# Sheet2.net
KiCad netlist of a schematic drawn in Altium Designer
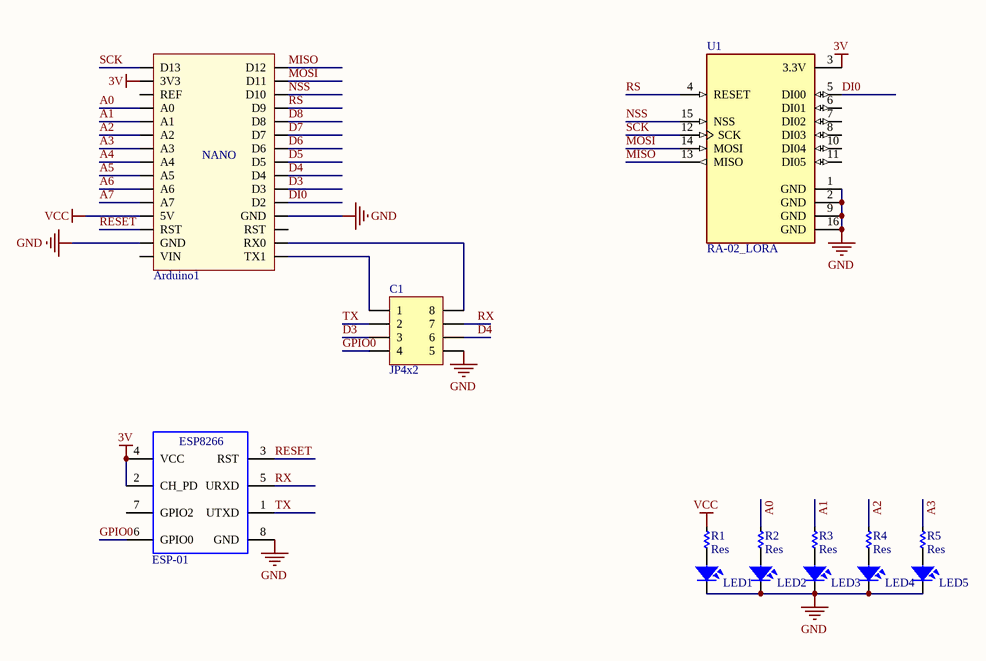
[diagram p0: Sheet2.SchDoc]

(export (version "E")
  (design (tool "Eeschema 10.0.6"))
  (components
    (comp (ref "Arduino1")
      (value "Arduino Nano")
      (footprint "Arduino Nano")
      (description "Arduino NANO")
      (libsource (lib "LIBRARY") (part "Arduino Nano"))
    )
    (comp (ref "C1")
      (value "JP4x2")
      (footprint "JP4-D2T")
      (description "WR-PHD 2.54 mm Dual Socket Header")
      (fields
        (field (name "MANUFACTURER") "Würth Elektronik eiSos GmbH")
        (field (name "PARTNO") "61300821821")
        (field (name "CREATED BY") "Karrer Zheng")
      )
      (libsource (lib "LIBRARY") (part "JP4x2"))
    )
    (comp (ref "LED1")
      (value "LED")
      (footprint "LED-5-Yellow")
      (description "LED Single colour Green and Red")
      (libsource (lib "LIBRARY") (part "LED"))
    )
    (comp (ref "LED2")
      (value "LED")
      (footprint "LED-5-Yellow")
      (description "LED Single colour Green and Red")
      (libsource (lib "LIBRARY") (part "LED"))
    )
    (comp (ref "LED3")
      (value "LED")
      (footprint "LED-5-Yellow")
      (description "LED Single colour Green and Red")
      (libsource (lib "LIBRARY") (part "LED"))
    )
    (comp (ref "LED4")
      (value "LED")
      (footprint "LED-5-Yellow")
      (description "LED Single colour Green and Red")
      (libsource (lib "LIBRARY") (part "LED"))
    )
    (comp (ref "LED5")
      (value "LED")
      (footprint "LED-5-Yellow")
      (description "LED Single colour Green and Red")
      (libsource (lib "LIBRARY") (part "LED"))
    )
    (comp (ref "R1")
      (value "Res")
      (footprint "RES-1/4WD")
      (fields
        (field (name "MANUFACTURER") "Generic Components")
        (field (name "PUBLISHER") "Altium Hobart Technology Centre")
      )
      (libsource (lib "LIBRARY") (part "Res"))
    )
    (comp (ref "R2")
      (value "Res")
      (footprint "RES-1/4WD")
      (fields
        (field (name "MANUFACTURER") "Generic Components")
        (field (name "PUBLISHER") "Altium Hobart Technology Centre")
      )
      (libsource (lib "LIBRARY") (part "Res"))
    )
    (comp (ref "R3")
      (value "Res")
      (footprint "RES-1/4WD")
      (fields
        (field (name "MANUFACTURER") "Generic Components")
        (field (name "PUBLISHER") "Altium Hobart Technology Centre")
      )
      (libsource (lib "LIBRARY") (part "Res"))
    )
    (comp (ref "R4")
      (value "Res")
      (footprint "RES-1/4WD")
      (fields
        (field (name "MANUFACTURER") "Generic Components")
        (field (name "PUBLISHER") "Altium Hobart Technology Centre")
      )
      (libsource (lib "LIBRARY") (part "Res"))
    )
    (comp (ref "R5")
      (value "Res")
      (footprint "RES-1/4WD")
      (fields
        (field (name "MANUFACTURER") "Generic Components")
        (field (name "PUBLISHER") "Altium Hobart Technology Centre")
      )
      (libsource (lib "LIBRARY") (part "Res"))
    )
    (comp (ref "U1")
      (value "RA-02_LORA")
      (footprint "MODULE_RA-02_LORA")
      (description "Ra-02 LoRa RF M5Stack Platform Evaluation Expansion Board")
      (fields (field (name "MP") "Ra-02 LoRa") (field (name "MF") "AI-Thinker"))
      (libsource (lib "RA-02_LORA") (part "RA-02_LORA"))
    )
    (comp (ref "U2")
      (value "ESP-01")
      (footprint "ESP8266")
      (description "ESP-12 Wi-Fi Module")
      (libsource (lib "LIBRARY") (part "ESP8266-01"))
    )
  )
  (nets
    (net (code "1") (name "/A0") (class "Default")
      (node (ref "Arduino1") (pin "A0") (pinfunction "A0_A0") (pintype "passive"))
      (node (ref "R2") (pin "1") (pinfunction "1_1") (pintype "passive"))
    )
    (net (code "2") (name "/A1") (class "Default")
      (node (ref "Arduino1") (pin "A1") (pinfunction "A1_A1") (pintype "passive"))
      (node (ref "R3") (pin "1") (pinfunction "1_1") (pintype "passive"))
    )
    (net (code "3") (name "/A2") (class "Default")
      (node (ref "Arduino1") (pin "A2") (pinfunction "A2_A2") (pintype "passive"))
      (node (ref "R4") (pin "1") (pinfunction "1_1") (pintype "passive"))
    )
    (net (code "4") (name "/A3") (class "Default")
      (node (ref "Arduino1") (pin "A3") (pinfunction "A3_A3") (pintype "passive"))
      (node (ref "R5") (pin "1") (pinfunction "1_1") (pintype "passive"))
    )
    (net (code "5") (name "/A4") (class "Default")
      (node (ref "Arduino1") (pin "A4") (pinfunction "A4_A4") (pintype "passive"))
    )
    (net (code "6") (name "/A5") (class "Default")
      (node (ref "Arduino1") (pin "A5") (pinfunction "A5_A5") (pintype "passive"))
    )
    (net (code "7") (name "/A6") (class "Default")
      (node (ref "Arduino1") (pin "A6") (pinfunction "A6_A6") (pintype "passive"))
    )
    (net (code "8") (name "/A7") (class "Default")
      (node (ref "Arduino1") (pin "A7") (pinfunction "A7_A7") (pintype "passive"))
    )
    (net (code "9") (name "/D3") (class "Default")
      (node (ref "Arduino1") (pin "D3") (pinfunction "D3_D3") (pintype "passive"))
      (node (ref "C1") (pin "3") (pinfunction "3_3") (pintype "passive"))
    )
    (net (code "10") (name "/D4") (class "Default")
      (node (ref "Arduino1") (pin "D4") (pinfunction "D4_D4") (pintype "passive"))
      (node (ref "C1") (pin "6") (pinfunction "6_6") (pintype "passive"))
    )
    (net (code "11") (name "/D5") (class "Default")
      (node (ref "Arduino1") (pin "D5") (pinfunction "D5_D5") (pintype "passive"))
    )
    (net (code "12") (name "/D6") (class "Default")
      (node (ref "Arduino1") (pin "D6") (pinfunction "D6_D6") (pintype "passive"))
    )
    (net (code "13") (name "/D7") (class "Default")
      (node (ref "Arduino1") (pin "D7") (pinfunction "D7_D7") (pintype "passive"))
    )
    (net (code "14") (name "/D8") (class "Default")
      (node (ref "Arduino1") (pin "D8") (pinfunction "D8_D8") (pintype "passive"))
    )
    (net (code "15") (name "/DI0") (class "Default")
      (node (ref "Arduino1") (pin "D2") (pinfunction "D2_D2") (pintype "passive"))
      (node (ref "U1") (pin "5") (pinfunction "DI00_5") (pintype "bidirectional"))
    )
    (net (code "16") (name "/GPIO0") (class "Default")
      (node (ref "C1") (pin "4") (pinfunction "4_4") (pintype "passive"))
      (node (ref "U2") (pin "6") (pinfunction "GPIO0_6") (pintype "passive"))
    )
    (net (code "17") (name "/MISO") (class "Default")
      (node (ref "Arduino1") (pin "D12") (pinfunction "D12_D12") (pintype "passive"))
      (node (ref "U1") (pin "13") (pinfunction "MISO_13") (pintype "output"))
    )
    (net (code "18") (name "/MOSI") (class "Default")
      (node (ref "Arduino1") (pin "D11") (pinfunction "D11_D11") (pintype "passive"))
      (node (ref "U1") (pin "14") (pinfunction "MOSI_14") (pintype "input"))
    )
    (net (code "19") (name "/NSS") (class "Default")
      (node (ref "Arduino1") (pin "D10") (pinfunction "D10_D10") (pintype "passive"))
      (node (ref "U1") (pin "15") (pinfunction "NSS_15") (pintype "input"))
    )
    (net (code "20") (name "/RESET") (class "Default")
      (node (ref "Arduino1") (pin "RST") (pinfunction "RST_RST") (pintype "passive"))
      (node (ref "U2") (pin "3") (pinfunction "RST_3") (pintype "passive"))
    )
    (net (code "21") (name "/RS") (class "Default")
      (node (ref "Arduino1") (pin "D9") (pinfunction "D9_D9") (pintype "passive"))
      (node (ref "U1") (pin "4") (pinfunction "RESET_4") (pintype "input"))
    )
    (net (code "22") (name "/RX") (class "Default")
      (node (ref "C1") (pin "7") (pinfunction "7_7") (pintype "passive"))
      (node (ref "U2") (pin "5") (pinfunction "URXD_5") (pintype "passive"))
    )
    (net (code "23") (name "/SCK") (class "Default")
      (node (ref "Arduino1") (pin "D13") (pinfunction "D13_D13") (pintype "passive"))
      (node (ref "U1") (pin "12") (pinfunction "SCK_12") (pintype "input"))
    )
    (net (code "24") (name "/TX") (class "Default")
      (node (ref "C1") (pin "2") (pinfunction "2_2") (pintype "passive"))
      (node (ref "U2") (pin "1") (pinfunction "UTXD_1") (pintype "passive"))
    )
    (net (code "25") (name "3V") (class "Default")
      (node (ref "Arduino1") (pin "3V3") (pinfunction "3V3_3V3") (pintype "passive"))
      (node (ref "U1") (pin "3") (pinfunction "3.3V_3") (pintype "power_in"))
      (node (ref "U2") (pin "2") (pinfunction "CH_PD_2") (pintype "passive"))
      (node (ref "U2") (pin "4") (pinfunction "VCC_4") (pintype "passive"))
    )
    (net (code "26") (name "GND") (class "Default")
      (node (ref "Arduino1") (pin "GND") (pinfunction "GND_GND") (pintype "passive"))
      (node (ref "C1") (pin "5") (pinfunction "5_5") (pintype "passive"))
      (node (ref "LED1") (pin "2") (pinfunction "2_2") (pintype "passive"))
      (node (ref "LED2") (pin "2") (pinfunction "2_2") (pintype "passive"))
      (node (ref "LED3") (pin "2") (pinfunction "2_2") (pintype "passive"))
      (node (ref "LED4") (pin "2") (pinfunction "2_2") (pintype "passive"))
      (node (ref "LED5") (pin "2") (pinfunction "2_2") (pintype "passive"))
      (node (ref "U1") (pin "1") (pinfunction "GND_1") (pintype "power_in"))
      (node (ref "U1") (pin "16") (pinfunction "GND_16") (pintype "power_in"))
      (node (ref "U1") (pin "2") (pinfunction "GND_2") (pintype "power_in"))
      (node (ref "U1") (pin "9") (pinfunction "GND_9") (pintype "power_in"))
      (node (ref "U2") (pin "8") (pinfunction "GND_8") (pintype "passive"))
    )
    (net (code "27") (name "Net-(Arduino1-PadRX0)") (class "Default")
      (node (ref "Arduino1") (pin "RX0") (pinfunction "RX0_RX0") (pintype "passive"))
      (node (ref "C1") (pin "8") (pinfunction "8_8") (pintype "passive"))
    )
    (net (code "28") (name "Net-(Arduino1-PadTX1)") (class "Default")
      (node (ref "Arduino1") (pin "TX1") (pinfunction "TX1_TX1") (pintype "passive"))
      (node (ref "C1") (pin "1") (pinfunction "1_1") (pintype "passive"))
    )
    (net (code "29") (name "Net-(LED1-Pad1)") (class "Default")
      (node (ref "LED1") (pin "1") (pinfunction "1_1") (pintype "passive"))
      (node (ref "R1") (pin "2") (pinfunction "2_2") (pintype "passive"))
    )
    (net (code "30") (name "Net-(LED2-Pad1)") (class "Default")
      (node (ref "LED2") (pin "1") (pinfunction "1_1") (pintype "passive"))
      (node (ref "R2") (pin "2") (pinfunction "2_2") (pintype "passive"))
    )
    (net (code "31") (name "Net-(LED3-Pad1)") (class "Default")
      (node (ref "LED3") (pin "1") (pinfunction "1_1") (pintype "passive"))
      (node (ref "R3") (pin "2") (pinfunction "2_2") (pintype "passive"))
    )
    (net (code "32") (name "Net-(LED4-Pad1)") (class "Default")
      (node (ref "LED4") (pin "1") (pinfunction "1_1") (pintype "passive"))
      (node (ref "R4") (pin "2") (pinfunction "2_2") (pintype "passive"))
    )
    (net (code "33") (name "Net-(LED5-Pad1)") (class "Default")
      (node (ref "LED5") (pin "1") (pinfunction "1_1") (pintype "passive"))
      (node (ref "R5") (pin "2") (pinfunction "2_2") (pintype "passive"))
    )
    (net (code "34") (name "VCC") (class "Default")
      (node (ref "Arduino1") (pin "5V") (pinfunction "5V_5V") (pintype "passive"))
      (node (ref "R1") (pin "1") (pinfunction "1_1") (pintype "passive"))
    )
    (net (code "35") (name "unconnected-(Arduino1-PadREF)") (class "Default")
      (node (ref "Arduino1") (pin "REF") (pinfunction "REF_REF") (pintype "passive"))
    )
    (net (code "36") (name "unconnected-(Arduino1-PadRST)") (class "Default")
      (node (ref "Arduino1") (pin "RST") (pinfunction "RST_RST") (pintype "passive"))
    )
    (net (code "37") (name "unconnected-(Arduino1-PadVIN)") (class "Default")
      (node (ref "Arduino1") (pin "VIN") (pinfunction "VIN_VIN") (pintype "passive"))
    )
    (net (code "38") (name "unconnected-(U1-DI01-Pad6)") (class "Default")
      (node (ref "U1") (pin "6") (pinfunction "DI01_6") (pintype "bidirectional"))
    )
    (net (code "39") (name "unconnected-(U1-DI02-Pad7)") (class "Default")
      (node (ref "U1") (pin "7") (pinfunction "DI02_7") (pintype "bidirectional"))
    )
    (net (code "40") (name "unconnected-(U1-DI03-Pad8)") (class "Default")
      (node (ref "U1") (pin "8") (pinfunction "DI03_8") (pintype "bidirectional"))
    )
    (net (code "41") (name "unconnected-(U1-DI04-Pad10)") (class "Default")
      (node (ref "U1") (pin "10") (pinfunction "DI04_10") (pintype "bidirectional"))
    )
    (net (code "42") (name "unconnected-(U1-DI05-Pad11)") (class "Default")
      (node (ref "U1") (pin "11") (pinfunction "DI05_11") (pintype "bidirectional"))
    )
    (net (code "43") (name "unconnected-(U2-GPIO2-Pad7)") (class "Default")
      (node (ref "U2") (pin "7") (pinfunction "GPIO2_7") (pintype "passive"))
    )
  )
)
